# ProPrj_OSBDM_HPM5301_2024-08-18.net
KiCad netlist of a schematic drawn in EasyEDA Pro
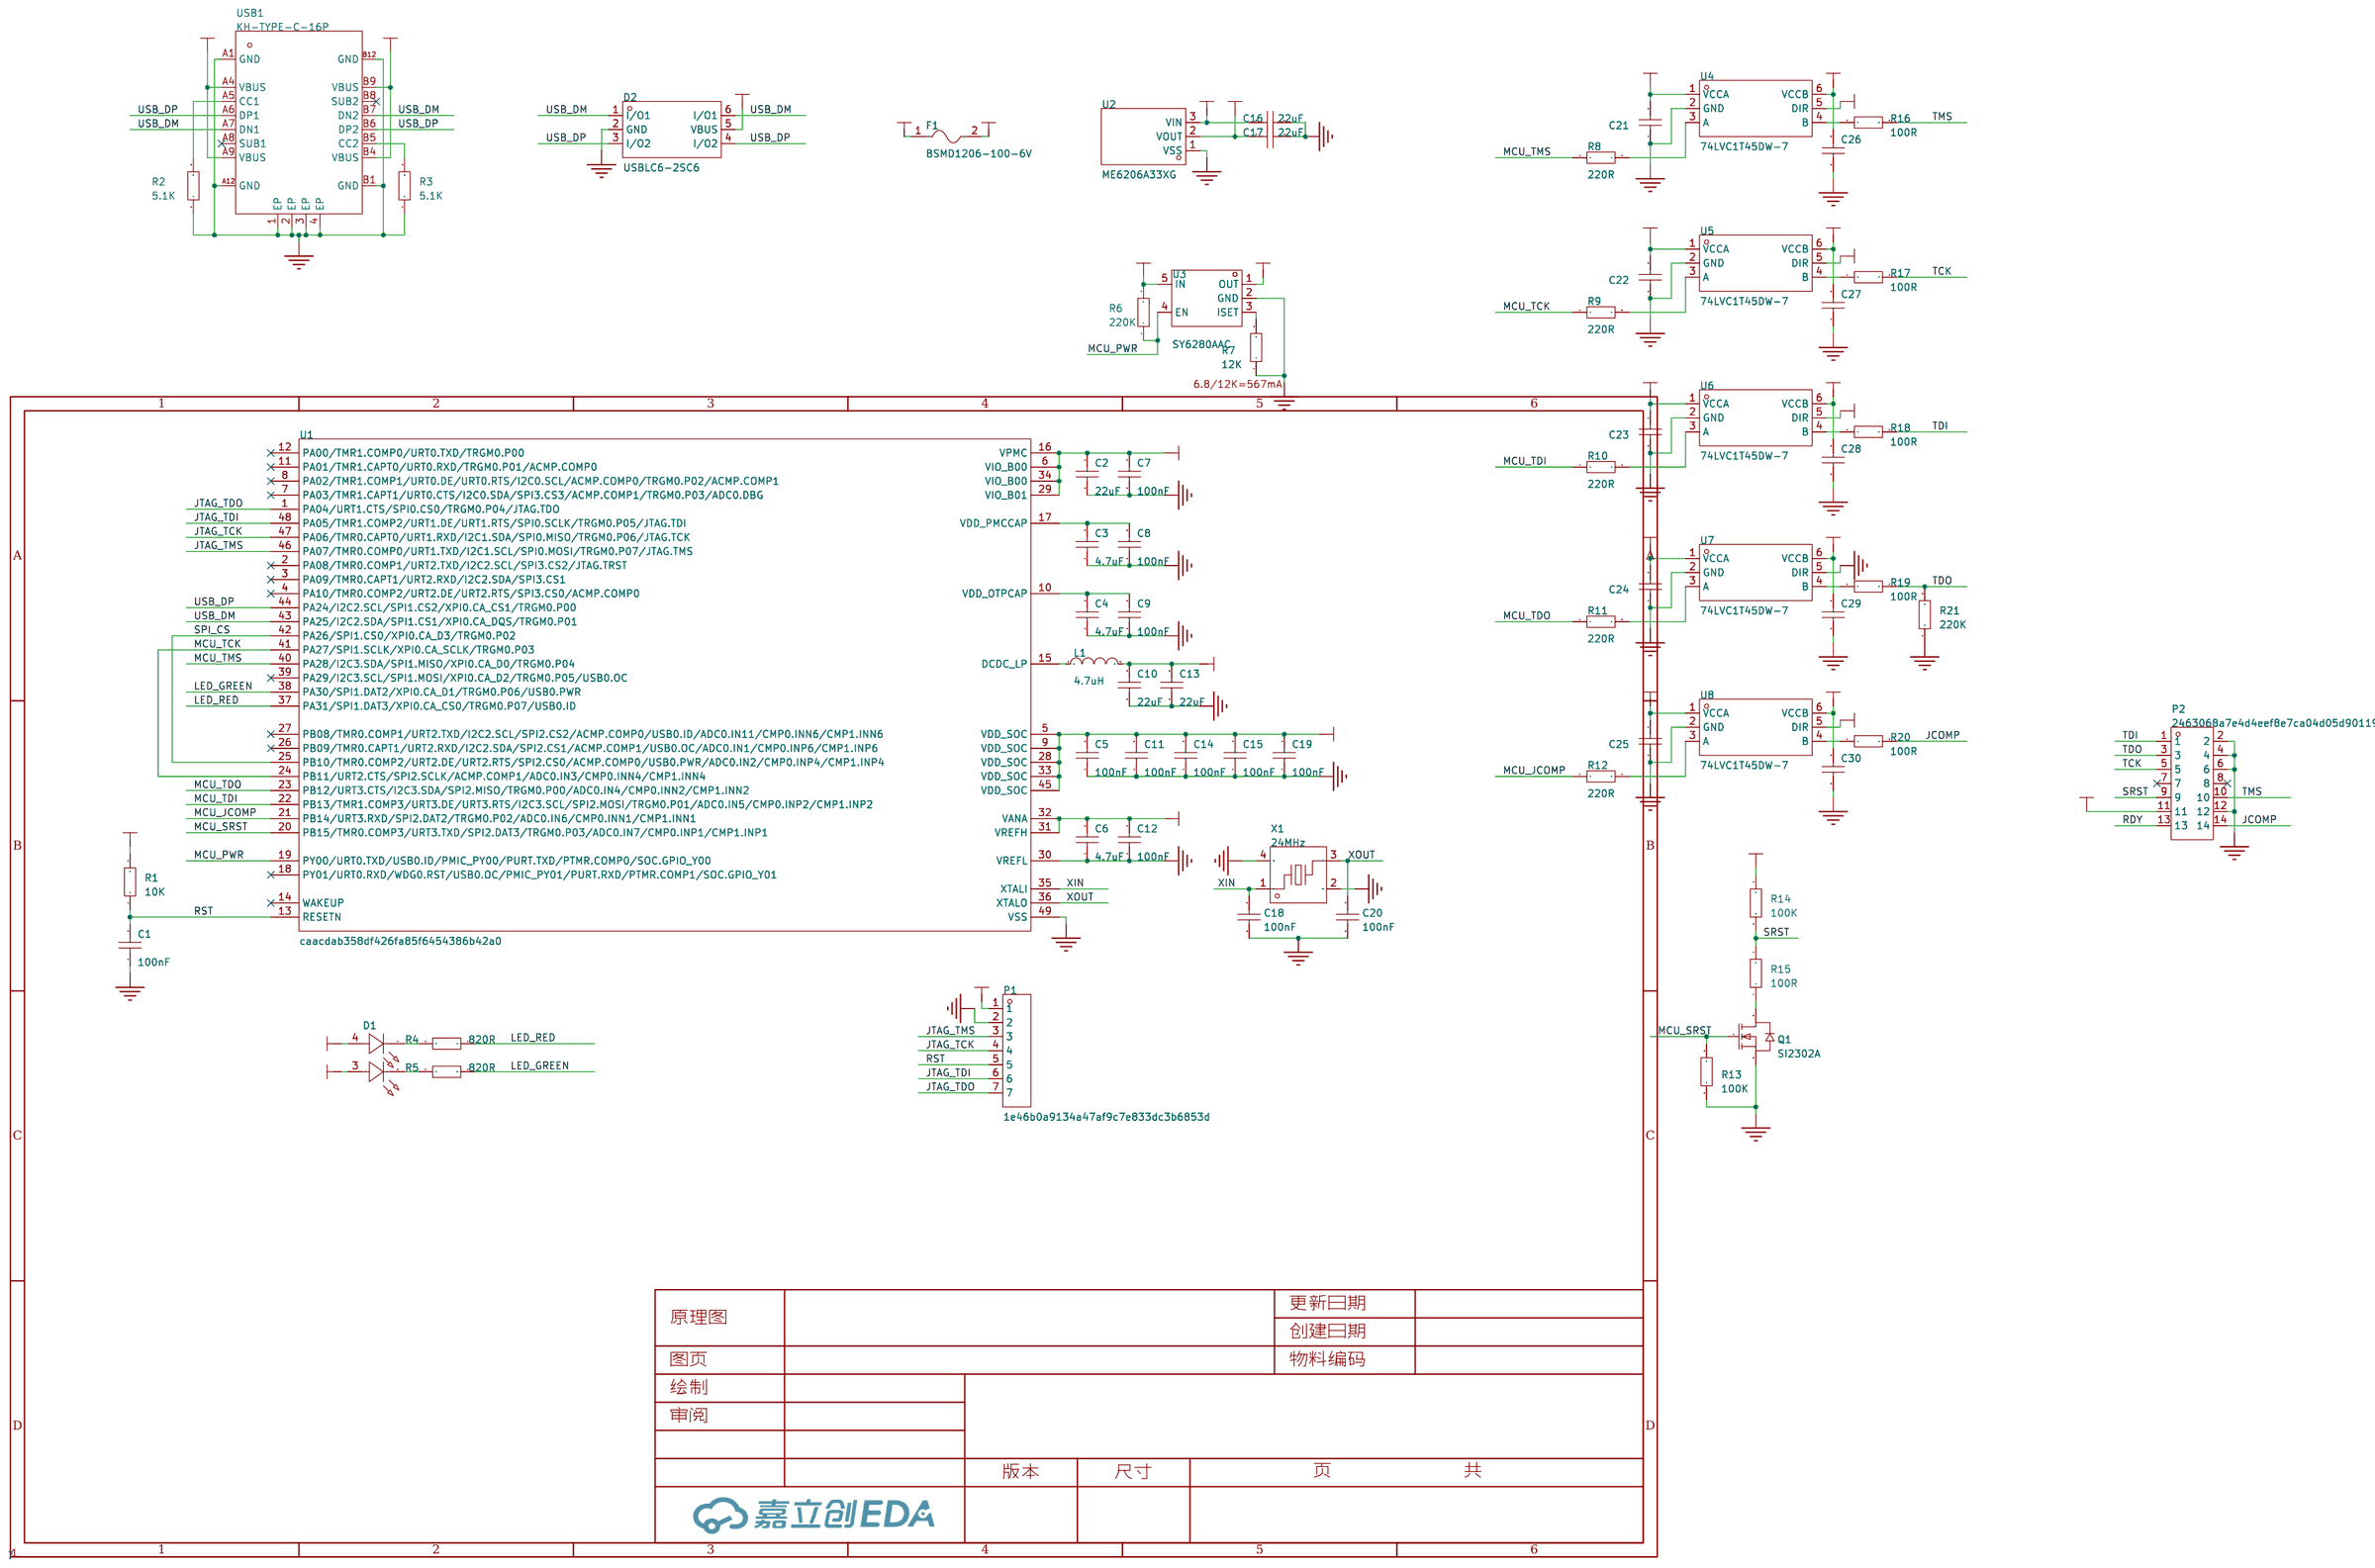
[diagram p0: schematic sheet]

(export (version "E")
  (design (tool "Eeschema 10.0.6"))
  (components
    (comp (ref "C1")
      (value "100nF")
      (footprint "easyedapro:C0603")
      (libsource (lib "easyedapro") (part "C0603"))
    )
    (comp (ref "C2")
      (value "22uF")
      (footprint "easyedapro:C0603")
      (libsource (lib "easyedapro") (part "C0603"))
    )
    (comp (ref "C3")
      (value "4.7uF")
      (footprint "easyedapro:C0603")
      (libsource (lib "easyedapro") (part "C0603"))
    )
    (comp (ref "C4")
      (value "4.7uF")
      (footprint "easyedapro:C0603")
      (libsource (lib "easyedapro") (part "C0603"))
    )
    (comp (ref "C5")
      (value "100nF")
      (footprint "easyedapro:C0603")
      (libsource (lib "easyedapro") (part "C0603"))
    )
    (comp (ref "C6")
      (value "4.7uF")
      (footprint "easyedapro:C0603")
      (libsource (lib "easyedapro") (part "C0603"))
    )
    (comp (ref "C7")
      (value "100nF")
      (footprint "easyedapro:C0603")
      (libsource (lib "easyedapro") (part "C0603"))
    )
    (comp (ref "C8")
      (value "100nF")
      (footprint "easyedapro:C0603")
      (libsource (lib "easyedapro") (part "C0603"))
    )
    (comp (ref "C9")
      (value "100nF")
      (footprint "easyedapro:C0603")
      (libsource (lib "easyedapro") (part "C0603"))
    )
    (comp (ref "C10")
      (value "22uF")
      (footprint "easyedapro:C0603")
      (libsource (lib "easyedapro") (part "C0603"))
    )
    (comp (ref "C11")
      (value "100nF")
      (footprint "easyedapro:C0603")
      (libsource (lib "easyedapro") (part "C0603"))
    )
    (comp (ref "C12")
      (value "100nF")
      (footprint "easyedapro:C0603")
      (libsource (lib "easyedapro") (part "C0603"))
    )
    (comp (ref "C13")
      (value "22uF")
      (footprint "easyedapro:C0603")
      (libsource (lib "easyedapro") (part "C0603"))
    )
    (comp (ref "C14")
      (value "100nF")
      (footprint "easyedapro:C0603")
      (libsource (lib "easyedapro") (part "C0603"))
    )
    (comp (ref "C15")
      (value "100nF")
      (footprint "easyedapro:C0603")
      (libsource (lib "easyedapro") (part "C0603"))
    )
    (comp (ref "C16")
      (value "22uF")
      (footprint "easyedapro:C0603")
      (libsource (lib "easyedapro") (part "C0603"))
    )
    (comp (ref "C17")
      (value "22uF")
      (footprint "easyedapro:C0603")
      (libsource (lib "easyedapro") (part "C0603"))
    )
    (comp (ref "C18")
      (value "100nF")
      (footprint "easyedapro:C0603")
      (libsource (lib "easyedapro") (part "C0603"))
    )
    (comp (ref "C19")
      (value "100nF")
      (footprint "easyedapro:C0603")
      (libsource (lib "easyedapro") (part "C0603"))
    )
    (comp (ref "C20")
      (value "100nF")
      (footprint "easyedapro:C0603")
      (libsource (lib "easyedapro") (part "C0603"))
    )
    (comp (ref "C21")
      (value "100nF")
      (footprint "easyedapro:C0603")
      (libsource (lib "easyedapro") (part "C0603"))
    )
    (comp (ref "C22")
      (value "100nF")
      (footprint "easyedapro:C0603")
      (libsource (lib "easyedapro") (part "C0603"))
    )
    (comp (ref "C23")
      (value "100nF")
      (footprint "easyedapro:C0603")
      (libsource (lib "easyedapro") (part "C0603"))
    )
    (comp (ref "C24")
      (value "100nF")
      (footprint "easyedapro:C0603")
      (libsource (lib "easyedapro") (part "C0603"))
    )
    (comp (ref "C25")
      (value "100nF")
      (footprint "easyedapro:C0603")
      (libsource (lib "easyedapro") (part "C0603"))
    )
    (comp (ref "C26")
      (value "100nF")
      (footprint "easyedapro:C0603")
      (libsource (lib "easyedapro") (part "C0603"))
    )
    (comp (ref "C27")
      (value "100nF")
      (footprint "easyedapro:C0603")
      (libsource (lib "easyedapro") (part "C0603"))
    )
    (comp (ref "C28")
      (value "100nF")
      (footprint "easyedapro:C0603")
      (libsource (lib "easyedapro") (part "C0603"))
    )
    (comp (ref "C29")
      (value "100nF")
      (footprint "easyedapro:C0603")
      (libsource (lib "easyedapro") (part "C0603"))
    )
    (comp (ref "C30")
      (value "100nF")
      (footprint "easyedapro:C0603")
      (libsource (lib "easyedapro") (part "C0603"))
    )
    (comp (ref "D1")
      (value "~")
      (footprint "easyedapro:LED1615")
      (libsource (lib "easyedapro") (part "LED1615"))
    )
    (comp (ref "D2")
      (value "USBLC6-2SC6")
      (footprint "easyedapro:SOT-23-6_L2.9-W1.6-P0.95-LS2.8-BL")
      (description "最大钳位电压:15V;击穿电压:6V;")
      (fields (field (name "Manufacturer") "UMW(友台半导体)"))
      (libsource (lib "easyedapro") (part "USBLC6-2SC6_C2687116"))
    )
    (comp (ref "F1")
      (value "BSMD1206-100-6V")
      (footprint "easyedapro:F1206")
      (description "最大电压:6V;最大电流:100A;保持电流:1A;跳闸电流:1.8A;")
      (fields (field (name "Manufacturer") "BHFUSE(佰宏)"))
      (libsource (lib "easyedapro") (part "BSMD1206-100-6V"))
    )
    (comp (ref "L1")
      (value "4.7uH")
      (footprint "easyedapro:IND-SMD_L2.5-W2.0")
      (description "电感值:4.7uH;精度:±20%;额定电流:840mA;饱和电流(Isat):1.25A;类型:-;")
      (fields
        (field (name "Manufacturer Part") "SWPA252012S4R7MT")
        (field (name "Manufacturer") "Sunlord(顺络)")
      )
      (libsource (lib "easyedapro") (part "SWPA252012S4R7MT"))
    )
    (comp (ref "P1")
      (value "1e46b0a9134a47af9c7e833dc3b6853d")
      (footprint "easyedapro:HDR-TH_7P-P1.27-V-M-1")
      (libsource (lib "easyedapro") (part "HDR1x7_1.27"))
    )
    (comp (ref "P2")
      (value "2463068a7e4d4eef8e7ca04d05d90119")
      (footprint "easyedapro:IDC-TH_14P-P1.27-H-F-R2-C7-W7.7")
      (description "间距：1.27mm 简牛座 弯插 2x7P 额定电流:1A，耐压:500V,工作温度范围:-40°C~+105°C")
      (libsource (lib "easyedapro") (part "IDC1.27-UD2S-7AH4.7"))
    )
    (comp (ref "Q1")
      (value "SI2302A")
      (footprint "easyedapro:SOT-23-3_L2.9-W1.3-P1.90-LS2.4-BR")
      (fields (field (name "Manufacturer") "UMW(友台半导体)"))
      (libsource (lib "easyedapro") (part "SI2302A"))
    )
    (comp (ref "R1") (value "10K") (libsource (lib "easyedapro") (part "R0402")))
    (comp (ref "R2") (value "5.1K") (libsource (lib "easyedapro") (part "R0402")))
    (comp (ref "R3") (value "5.1K") (libsource (lib "easyedapro") (part "R0402")))
    (comp (ref "R4") (value "820R") (footprint "easyedapro:R0603") (libsource (lib "easyedapro") (part "电阻")))
    (comp (ref "R5") (value "820R") (footprint "easyedapro:R0603") (libsource (lib "easyedapro") (part "电阻")))
    (comp (ref "R6")
      (value "220K")
      (footprint "easyedapro:R0603")
      (libsource (lib "easyedapro") (part "R0603"))
    )
    (comp (ref "R7")
      (value "12K")
      (footprint "easyedapro:R0603")
      (libsource (lib "easyedapro") (part "R0603"))
    )
    (comp (ref "R8")
      (value "220R")
      (footprint "easyedapro:R0603")
      (libsource (lib "easyedapro") (part "R0603"))
    )
    (comp (ref "R9")
      (value "220R")
      (footprint "easyedapro:R0603")
      (libsource (lib "easyedapro") (part "R0603"))
    )
    (comp (ref "R10")
      (value "220R")
      (footprint "easyedapro:R0603")
      (libsource (lib "easyedapro") (part "R0603"))
    )
    (comp (ref "R11")
      (value "220R")
      (footprint "easyedapro:R0603")
      (libsource (lib "easyedapro") (part "R0603"))
    )
    (comp (ref "R12")
      (value "220R")
      (footprint "easyedapro:R0603")
      (libsource (lib "easyedapro") (part "R0603"))
    )
    (comp (ref "R13")
      (value "100K")
      (footprint "easyedapro:R0603")
      (libsource (lib "easyedapro") (part "电阻"))
    )
    (comp (ref "R14")
      (value "100K")
      (footprint "easyedapro:R0603")
      (libsource (lib "easyedapro") (part "电阻"))
    )
    (comp (ref "R15")
      (value "100R")
      (footprint "easyedapro:R0603")
      (libsource (lib "easyedapro") (part "电阻"))
    )
    (comp (ref "R16")
      (value "100R")
      (footprint "easyedapro:R0603")
      (libsource (lib "easyedapro") (part "R0603"))
    )
    (comp (ref "R17")
      (value "100R")
      (footprint "easyedapro:R0603")
      (libsource (lib "easyedapro") (part "R0603"))
    )
    (comp (ref "R18")
      (value "100R")
      (footprint "easyedapro:R0603")
      (libsource (lib "easyedapro") (part "R0603"))
    )
    (comp (ref "R19")
      (value "100R")
      (footprint "easyedapro:R0603")
      (libsource (lib "easyedapro") (part "R0603"))
    )
    (comp (ref "R20")
      (value "100R")
      (footprint "easyedapro:R0603")
      (libsource (lib "easyedapro") (part "R0603"))
    )
    (comp (ref "R21")
      (value "220K")
      (footprint "easyedapro:R0603")
      (libsource (lib "easyedapro") (part "R0603"))
    )
    (comp (ref "U1")
      (value "caacdab358df426fa85f6454386b42a0")
      (footprint "easyedapro:QFN-48_L6.0-W6.0-P0.4-BL-EP4.2")
      (libsource (lib "easyedapro") (part "HPM5301IEG1"))
    )
    (comp (ref "U2")
      (value "ME6206A33XG")
      (footprint "easyedapro:SOT-23-3_L2.9-W1.6-P1.90-LS2.8-BR")
      (description "输出类型:固定;最大输入电压:6V;输出电压:3.3V;最大输出电流:300mA;电源纹波抑制比(PSRR):50dB@(1kHz);输出极性:正极;")
      (fields (field (name "Manufacturer") "MICRONE(南京微盟)"))
      (libsource (lib "easyedapro") (part "ME6206A33XG"))
    )
    (comp (ref "U3")
      (value "SY6280AAC")
      (footprint "easyedapro:SOT-23-5_L3.0-W1.7-P0.95-LS2.8-BL")
      (description "低能耗配电开关")
      (fields (field (name "Manufacturer") "silergy(矽力杰)"))
      (libsource (lib "easyedapro") (part "SY6280AAC"))
    )
    (comp (ref "U4")
      (value "74LVC1T45DW-7")
      (footprint "easyedapro:SC-70-6_L2.2-W1.3-P0.65-LS2.1-BR")
      (description "电压(VCCA):1.65V~5.5V;电压(VCCB):1.65V~5.5V;电路数:1;每个电路通道数:1;")
      (fields (field (name "Manufacturer") "DIODES(美台)"))
      (libsource (lib "easyedapro") (part "74LVC1T45DW-7"))
    )
    (comp (ref "U5")
      (value "74LVC1T45DW-7")
      (footprint "easyedapro:SC-70-6_L2.2-W1.3-P0.65-LS2.1-BR")
      (description "电压(VCCA):1.65V~5.5V;电压(VCCB):1.65V~5.5V;电路数:1;每个电路通道数:1;")
      (fields (field (name "Manufacturer") "DIODES(美台)"))
      (libsource (lib "easyedapro") (part "74LVC1T45DW-7"))
    )
    (comp (ref "U6")
      (value "74LVC1T45DW-7")
      (footprint "easyedapro:SC-70-6_L2.2-W1.3-P0.65-LS2.1-BR")
      (description "电压(VCCA):1.65V~5.5V;电压(VCCB):1.65V~5.5V;电路数:1;每个电路通道数:1;")
      (fields (field (name "Manufacturer") "DIODES(美台)"))
      (libsource (lib "easyedapro") (part "74LVC1T45DW-7"))
    )
    (comp (ref "U7")
      (value "74LVC1T45DW-7")
      (footprint "easyedapro:SC-70-6_L2.2-W1.3-P0.65-LS2.1-BR")
      (description "电压(VCCA):1.65V~5.5V;电压(VCCB):1.65V~5.5V;电路数:1;每个电路通道数:1;")
      (fields (field (name "Manufacturer") "DIODES(美台)"))
      (libsource (lib "easyedapro") (part "74LVC1T45DW-7"))
    )
    (comp (ref "U8")
      (value "74LVC1T45DW-7")
      (footprint "easyedapro:SC-70-6_L2.2-W1.3-P0.65-LS2.1-BR")
      (description "电压(VCCA):1.65V~5.5V;电压(VCCB):1.65V~5.5V;电路数:1;每个电路通道数:1;")
      (fields (field (name "Manufacturer") "DIODES(美台)"))
      (libsource (lib "easyedapro") (part "74LVC1T45DW-7"))
    )
    (comp (ref "USB1")
      (value "KH-TYPE-C-16P")
      (footprint "easyedapro:USB-C-SMD_KH-TYPE-C-16P")
      (description "连接器类型:Type-C;标准:-;公母:母座;触点数量:16;端口数量:1;安装方式:卧贴;额定电流 - 电源:3A;工作温度范围:-40~+85;")
      (fields (field (name "Manufacturer") "kinghelm(金航标)"))
      (libsource (lib "easyedapro") (part "KH-TYPE-C-16P"))
    )
    (comp (ref "X1")
      (value "24MHz")
      (footprint "easyedapro:CRYSTAL-SMD_4P-L2.0-W1.6-BL-A")
      (description "晶振类型:贴片晶振;频率:24MHz;常温频差:±10ppm;外接负载电容:8pF;频率稳定度(全温):±20ppm;")
      (fields
        (field (name "Manufacturer Part") "XL7EL89CKI-111YLC-24M")
        (field (name "Manufacturer") "YXC(扬兴晶振)")
      )
      (libsource (lib "easyedapro") (part "XL7EL89CKI-111YLC-24M"))
    )
  )
  (nets
    (net (code "1") (name "/JCOMP") (class "Default")
      (node (ref "P2") (pin "14") (pinfunction "14_14") (pintype "unspecified"))
      (node (ref "R20") (pin "2") (pinfunction "2_2") (pintype "input"))
    )
    (net (code "2") (name "/JTAG_TCK") (class "Default")
      (node (ref "P1") (pin "4") (pinfunction "4_4") (pintype "unspecified"))
      (node (ref "U1") (pin "47") (pinfunction "PA06/TMR0.CAPT0/URT1.RXD/I2C1.SDA/SPI0.MISO/TRGM0.P06/JTAG.TCK_47") (pintype "bidirectional"))
    )
    (net (code "3") (name "/JTAG_TDI") (class "Default")
      (node (ref "P1") (pin "6") (pinfunction "6_6") (pintype "unspecified"))
      (node (ref "U1") (pin "48") (pinfunction "PA05/TMR1.COMP2/URT1.DE/URT1.RTS/SPI0.SCLK/TRGM0.P05/JTAG.TDI_48") (pintype "bidirectional"))
    )
    (net (code "4") (name "/JTAG_TDO") (class "Default")
      (node (ref "P1") (pin "7") (pinfunction "7_7") (pintype "unspecified"))
      (node (ref "U1") (pin "1") (pinfunction "PA04/URT1.CTS/SPI0.CS0/TRGM0.P04/JTAG.TDO_1") (pintype "bidirectional"))
    )
    (net (code "5") (name "/JTAG_TMS") (class "Default")
      (node (ref "P1") (pin "3") (pinfunction "3_3") (pintype "unspecified"))
      (node (ref "U1") (pin "46") (pinfunction "PA07/TMR0.COMP0/URT1.TXD/I2C1.SCL/SPI0.MOSI/TRGM0.P07/JTAG.TMS_46") (pintype "bidirectional"))
    )
    (net (code "6") (name "/LED_GREEN") (class "Default")
      (node (ref "R5") (pin "1") (pinfunction "1_1") (pintype "input"))
      (node (ref "U1") (pin "38") (pinfunction "PA30/SPI1.DAT2/XPI0.CA_D1/TRGM0.P06/USB0.PWR_38") (pintype "bidirectional"))
    )
    (net (code "7") (name "/LED_RED") (class "Default")
      (node (ref "R4") (pin "1") (pinfunction "1_1") (pintype "input"))
      (node (ref "U1") (pin "37") (pinfunction "PA31/SPI1.DAT3/XPI0.CA_CS0/TRGM0.P07/USB0.ID_37") (pintype "bidirectional"))
    )
    (net (code "8") (name "/MCU_JCOMP") (class "Default")
      (node (ref "R12") (pin "1") (pinfunction "1_1") (pintype "input"))
      (node (ref "U1") (pin "21") (pinfunction "PB14/URT3.RXD/SPI2.DAT2/TRGM0.P02/ADC0.IN6/CMP0.INN1/CMP1.INN1_21") (pintype "bidirectional"))
    )
    (net (code "9") (name "/MCU_PWR") (class "Default")
      (node (ref "R6") (pin "1") (pinfunction "1_1") (pintype "input"))
      (node (ref "U1") (pin "19") (pinfunction "PY00/URT0.TXD/USB0.ID/PMIC_PY00/PURT.TXD/PTMR.COMP0/SOC.GPIO_Y00_19") (pintype "bidirectional"))
      (node (ref "U3") (pin "4") (pinfunction "EN_4") (pintype "unspecified"))
    )
    (net (code "10") (name "/MCU_SRST") (class "Default")
      (node (ref "Q1") (pin "1") (pinfunction "G_1") (pintype "unspecified"))
      (node (ref "R13") (pin "1") (pinfunction "1_1") (pintype "input"))
      (node (ref "U1") (pin "20") (pinfunction "PB15/TMR0.COMP3/URT3.TXD/SPI2.DAT3/TRGM0.P03/ADC0.IN7/CMP0.INP1/CMP1.INP1_20") (pintype "bidirectional"))
    )
    (net (code "11") (name "/MCU_TCK") (class "Default")
      (node (ref "R9") (pin "1") (pinfunction "1_1") (pintype "input"))
      (node (ref "U1") (pin "24") (pinfunction "PB11/URT2.CTS/SPI2.SCLK/ACMP.COMP1/ADC0.IN3/CMP0.INN4/CMP1.INN4_24") (pintype "bidirectional"))
      (node (ref "U1") (pin "41") (pinfunction "PA27/SPI1.SCLK/XPI0.CA_SCLK/TRGM0.P03_41") (pintype "bidirectional"))
    )
    (net (code "12") (name "/MCU_TDI") (class "Default")
      (node (ref "R10") (pin "1") (pinfunction "1_1") (pintype "input"))
      (node (ref "U1") (pin "22") (pinfunction "PB13/TMR1.COMP3/URT3.DE/URT3.RTS/I2C3.SCL/SPI2.MOSI/TRGM0.P01/ADC0.IN5/CMP0.INP2/CMP1.INP2_22") (pintype "bidirectional"))
    )
    (net (code "13") (name "/MCU_TDO") (class "Default")
      (node (ref "R11") (pin "1") (pinfunction "1_1") (pintype "input"))
      (node (ref "U1") (pin "23") (pinfunction "PB12/URT3.CTS/I2C3.SDA/SPI2.MISO/TRGM0.P00/ADC0.IN4/CMP0.INN2/CMP1.INN2_23") (pintype "bidirectional"))
    )
    (net (code "14") (name "/MCU_TMS") (class "Default")
      (node (ref "R8") (pin "1") (pinfunction "1_1") (pintype "input"))
      (node (ref "U1") (pin "40") (pinfunction "PA28/I2C3.SDA/SPI1.MISO/XPI0.CA_D0/TRGM0.P04_40") (pintype "bidirectional"))
    )
    (net (code "15") (name "/RDY") (class "Default")
      (node (ref "P2") (pin "13") (pinfunction "13_13") (pintype "unspecified"))
    )
    (net (code "16") (name "/RST") (class "Default")
      (node (ref "C1") (pin "2") (pinfunction "2_2") (pintype "input"))
      (node (ref "P1") (pin "5") (pinfunction "5_5") (pintype "unspecified"))
      (node (ref "R1") (pin "1") (pinfunction "1_1") (pintype "input"))
      (node (ref "U1") (pin "13") (pinfunction "RESETN_13") (pintype "input"))
    )
    (net (code "17") (name "/SPI_CS") (class "Default")
      (node (ref "U1") (pin "25") (pinfunction "PB10/TMR0.COMP2/URT2.DE/URT2.RTS/SPI2.CS0/ACMP.COMP0/USB0.PWR/ADC0.IN2/CMP0.INP4/CMP1.INP4_25") (pintype "bidirectional"))
      (node (ref "U1") (pin "42") (pinfunction "PA26/SPI1.CS0/XPI0.CA_D3/TRGM0.P02_42") (pintype "bidirectional"))
    )
    (net (code "18") (name "/SRST") (class "Default")
      (node (ref "P2") (pin "9") (pinfunction "9_9") (pintype "unspecified"))
      (node (ref "R14") (pin "2") (pinfunction "2_2") (pintype "input"))
      (node (ref "R15") (pin "2") (pinfunction "2_2") (pintype "input"))
    )
    (net (code "19") (name "/TCK") (class "Default")
      (node (ref "P2") (pin "5") (pinfunction "5_5") (pintype "unspecified"))
      (node (ref "R17") (pin "2") (pinfunction "2_2") (pintype "input"))
    )
    (net (code "20") (name "/TDI") (class "Default")
      (node (ref "P2") (pin "1") (pinfunction "1_1") (pintype "unspecified"))
      (node (ref "R18") (pin "2") (pinfunction "2_2") (pintype "input"))
    )
    (net (code "21") (name "/TDO") (class "Default")
      (node (ref "P2") (pin "3") (pinfunction "3_3") (pintype "unspecified"))
      (node (ref "R19") (pin "2") (pinfunction "2_2") (pintype "input"))
      (node (ref "R21") (pin "2") (pinfunction "2_2") (pintype "input"))
    )
    (net (code "22") (name "/TMS") (class "Default")
      (node (ref "P2") (pin "10") (pinfunction "10_10") (pintype "unspecified"))
      (node (ref "R16") (pin "2") (pinfunction "2_2") (pintype "input"))
    )
    (net (code "23") (name "/USB_DM") (class "Default")
      (node (ref "D2") (pin "1") (pinfunction "I/O1_1") (pintype "unspecified"))
      (node (ref "D2") (pin "6") (pinfunction "I/O1_6") (pintype "unspecified"))
      (node (ref "U1") (pin "43") (pinfunction "PA25/I2C2.SDA/SPI1.CS1/XPI0.CA_DQS/TRGM0.P01_43") (pintype "bidirectional"))
      (node (ref "USB1") (pin "A7") (pinfunction "DN1_A7") (pintype "unspecified"))
      (node (ref "USB1") (pin "B7") (pinfunction "DN2_B7") (pintype "unspecified"))
    )
    (net (code "24") (name "/USB_DP") (class "Default")
      (node (ref "D2") (pin "3") (pinfunction "I/O2_3") (pintype "unspecified"))
      (node (ref "D2") (pin "4") (pinfunction "I/O2_4") (pintype "unspecified"))
      (node (ref "U1") (pin "44") (pinfunction "PA24/I2C2.SCL/SPI1.CS2/XPI0.CA_CS1/TRGM0.P00_44") (pintype "bidirectional"))
      (node (ref "USB1") (pin "A6") (pinfunction "DP1_A6") (pintype "unspecified"))
      (node (ref "USB1") (pin "B6") (pinfunction "DP2_B6") (pintype "unspecified"))
    )
    (net (code "25") (name "/XIN") (class "Default")
      (node (ref "C18") (pin "2") (pinfunction "2_2") (pintype "input"))
      (node (ref "U1") (pin "35") (pinfunction "XTALI_35") (pintype "input"))
      (node (ref "X1") (pin "1") (pinfunction "1_1") (pintype "input"))
    )
    (net (code "26") (name "/XOUT") (class "Default")
      (node (ref "C20") (pin "2") (pinfunction "2_2") (pintype "input"))
      (node (ref "U1") (pin "36") (pinfunction "XTALO_36") (pintype "output"))
      (node (ref "X1") (pin "3") (pinfunction "3_3") (pintype "input"))
    )
    (net (code "27") (name "3.3V") (class "Default")
      (node (ref "C12") (pin "2") (pinfunction "2_2") (pintype "input"))
      (node (ref "C17") (pin "2") (pinfunction "2_2") (pintype "input"))
      (node (ref "C2") (pin "2") (pinfunction "2_2") (pintype "input"))
      (node (ref "C21") (pin "2") (pinfunction "2_2") (pintype "input"))
      (node (ref "C22") (pin "2") (pinfunction "2_2") (pintype "input"))
      (node (ref "C23") (pin "2") (pinfunction "2_2") (pintype "input"))
      (node (ref "C24") (pin "2") (pinfunction "2_2") (pintype "input"))
      (node (ref "C25") (pin "2") (pinfunction "2_2") (pintype "input"))
      (node (ref "C6") (pin "2") (pinfunction "2_2") (pintype "input"))
      (node (ref "C7") (pin "2") (pinfunction "2_2") (pintype "input"))
      (node (ref "D1") (pin "3") (pinfunction "A_3") (pintype "unspecified"))
      (node (ref "D1") (pin "4") (pinfunction "A_4") (pintype "unspecified"))
      (node (ref "P1") (pin "1") (pinfunction "1_1") (pintype "unspecified"))
      (node (ref "R1") (pin "2") (pinfunction "2_2") (pintype "input"))
      (node (ref "U1") (pin "16") (pinfunction "VPMC_16") (pintype "unspecified"))
      (node (ref "U1") (pin "29") (pinfunction "VIO_B01_29") (pintype "unspecified"))
      (node (ref "U1") (pin "31") (pinfunction "VREFH_31") (pintype "unspecified"))
      (node (ref "U1") (pin "32") (pinfunction "VANA_32") (pintype "unspecified"))
      (node (ref "U1") (pin "34") (pinfunction "VIO_B00_34") (pintype "unspecified"))
      (node (ref "U1") (pin "6") (pinfunction "VIO_B00_6") (pintype "unspecified"))
      (node (ref "U2") (pin "2") (pinfunction "VOUT_2") (pintype "input"))
      (node (ref "U4") (pin "1") (pinfunction "VCCA_1") (pintype "unspecified"))
      (node (ref "U4") (pin "5") (pinfunction "DIR_5") (pintype "unspecified"))
      (node (ref "U5") (pin "1") (pinfunction "VCCA_1") (pintype "unspecified"))
      (node (ref "U5") (pin "5") (pinfunction "DIR_5") (pintype "unspecified"))
      (node (ref "U6") (pin "1") (pinfunction "VCCA_1") (pintype "unspecified"))
      (node (ref "U6") (pin "5") (pinfunction "DIR_5") (pintype "unspecified"))
      (node (ref "U7") (pin "1") (pinfunction "VCCA_1") (pintype "unspecified"))
      (node (ref "U8") (pin "1") (pinfunction "VCCA_1") (pintype "unspecified"))
      (node (ref "U8") (pin "5") (pinfunction "DIR_5") (pintype "unspecified"))
    )
    (net (code "28") (name "5V") (class "Default")
      (node (ref "C16") (pin "2") (pinfunction "2_2") (pintype "input"))
      (node (ref "F1") (pin "2") (pinfunction "2_2") (pintype "unspecified"))
      (node (ref "R6") (pin "2") (pinfunction "2_2") (pintype "input"))
      (node (ref "U2") (pin "3") (pinfunction "VIN_3") (pintype "input"))
      (node (ref "U3") (pin "5") (pinfunction "IN_5") (pintype "unspecified"))
    )
    (net (code "29") (name "GND") (class "Default")
      (node (ref "C1") (pin "1") (pinfunction "1_1") (pintype "input"))
      (node (ref "C10") (pin "1") (pinfunction "1_1") (pintype "input"))
      (node (ref "C11") (pin "1") (pinfunction "1_1") (pintype "input"))
      (node (ref "C12") (pin "1") (pinfunction "1_1") (pintype "input"))
      (node (ref "C13") (pin "1") (pinfunction "1_1") (pintype "input"))
      (node (ref "C14") (pin "1") (pinfunction "1_1") (pintype "input"))
      (node (ref "C15") (pin "1") (pinfunction "1_1") (pintype "input"))
      (node (ref "C16") (pin "1") (pinfunction "1_1") (pintype "input"))
      (node (ref "C17") (pin "1") (pinfunction "1_1") (pintype "input"))
      (node (ref "C18") (pin "1") (pinfunction "1_1") (pintype "input"))
      (node (ref "C19") (pin "1") (pinfunction "1_1") (pintype "input"))
      (node (ref "C2") (pin "1") (pinfunction "1_1") (pintype "input"))
      (node (ref "C20") (pin "1") (pinfunction "1_1") (pintype "input"))
      (node (ref "C21") (pin "1") (pinfunction "1_1") (pintype "input"))
      (node (ref "C22") (pin "1") (pinfunction "1_1") (pintype "input"))
      (node (ref "C23") (pin "1") (pinfunction "1_1") (pintype "input"))
      (node (ref "C24") (pin "1") (pinfunction "1_1") (pintype "input"))
      (node (ref "C25") (pin "1") (pinfunction "1_1") (pintype "input"))
      (node (ref "C26") (pin "1") (pinfunction "1_1") (pintype "input"))
      (node (ref "C27") (pin "1") (pinfunction "1_1") (pintype "input"))
      (node (ref "C28") (pin "1") (pinfunction "1_1") (pintype "input"))
      (node (ref "C29") (pin "1") (pinfunction "1_1") (pintype "input"))
      (node (ref "C3") (pin "1") (pinfunction "1_1") (pintype "input"))
      (node (ref "C30") (pin "1") (pinfunction "1_1") (pintype "input"))
      (node (ref "C4") (pin "1") (pinfunction "1_1") (pintype "input"))
      (node (ref "C5") (pin "1") (pinfunction "1_1") (pintype "input"))
      (node (ref "C6") (pin "1") (pinfunction "1_1") (pintype "input"))
      (node (ref "C7") (pin "1") (pinfunction "1_1") (pintype "input"))
      (node (ref "C8") (pin "1") (pinfunction "1_1") (pintype "input"))
      (node (ref "C9") (pin "1") (pinfunction "1_1") (pintype "input"))
      (node (ref "D2") (pin "2") (pinfunction "GND_2") (pintype "unspecified"))
      (node (ref "P1") (pin "2") (pinfunction "2_2") (pintype "unspecified"))
      (node (ref "P2") (pin "12") (pinfunction "12_12") (pintype "unspecified"))
      (node (ref "P2") (pin "2") (pinfunction "2_2") (pintype "unspecified"))
      (node (ref "P2") (pin "4") (pinfunction "4_4") (pintype "unspecified"))
      (node (ref "P2") (pin "6") (pinfunction "6_6") (pintype "unspecified"))
      (node (ref "Q1") (pin "2") (pinfunction "S_2") (pintype "unspecified"))
      (node (ref "R13") (pin "2") (pinfunction "2_2") (pintype "input"))
      (node (ref "R2") (pin "1") (pinfunction "1_1") (pintype "input"))
      (node (ref "R21") (pin "1") (pinfunction "1_1") (pintype "input"))
      (node (ref "R3") (pin "1") (pinfunction "1_1") (pintype "input"))
      (node (ref "R7") (pin "1") (pinfunction "1_1") (pintype "input"))
      (node (ref "U1") (pin "30") (pinfunction "VREFL_30") (pintype "unspecified"))
      (node (ref "U1") (pin "49") (pinfunction "VSS_49") (pintype "unspecified"))
      (node (ref "U2") (pin "1") (pinfunction "VSS_1") (pintype "input"))
      (node (ref "U3") (pin "2") (pinfunction "GND_2") (pintype "unspecified"))
      (node (ref "U4") (pin "2") (pinfunction "GND_2") (pintype "unspecified"))
      (node (ref "U5") (pin "2") (pinfunction "GND_2") (pintype "unspecified"))
      (node (ref "U6") (pin "2") (pinfunction "GND_2") (pintype "unspecified"))
      (node (ref "U7") (pin "2") (pinfunction "GND_2") (pintype "unspecified"))
      (node (ref "U7") (pin "5") (pinfunction "DIR_5") (pintype "unspecified"))
      (node (ref "U8") (pin "2") (pinfunction "GND_2") (pintype "unspecified"))
      (node (ref "USB1") (pin "1") (pinfunction "EP_1") (pintype "unspecified"))
      (node (ref "USB1") (pin "2") (pinfunction "EP_2") (pintype "unspecified"))
      (node (ref "USB1") (pin "3") (pinfunction "EP_3") (pintype "unspecified"))
      (node (ref "USB1") (pin "4") (pinfunction "EP_4") (pintype "unspecified"))
      (node (ref "USB1") (pin "A1") (pinfunction "GND_A1") (pintype "unspecified"))
      (node (ref "USB1") (pin "A12") (pinfunction "GND_A12") (pintype "unspecified"))
      (node (ref "USB1") (pin "B1") (pinfunction "GND_B1") (pintype "unspecified"))
      (node (ref "USB1") (pin "B12") (pinfunction "GND_B12") (pintype "unspecified"))
      (node (ref "X1") (pin "2") (pinfunction "GND_2") (pintype "input"))
      (node (ref "X1") (pin "4") (pinfunction "GND_4") (pintype "input"))
    )
    (net (code "30") (name "Net-(D1-K-Pad1)") (class "Default")
      (node (ref "D1") (pin "1") (pinfunction "K_1") (pintype "unspecified"))
      (node (ref "R4") (pin "2") (pinfunction "2_2") (pintype "input"))
    )
    (net (code "31") (name "Net-(D1-K-Pad2)") (class "Default")
      (node (ref "D1") (pin "2") (pinfunction "K_2") (pintype "unspecified"))
      (node (ref "R5") (pin "2") (pinfunction "2_2") (pintype "input"))
    )
    (net (code "32") (name "Net-(Q1-D)") (class "Default")
      (node (ref "Q1") (pin "3") (pinfunction "D_3") (pintype "unspecified"))
      (node (ref "R15") (pin "1") (pinfunction "1_1") (pintype "input"))
    )
    (net (code "33") (name "Net-(U1-DCDC_LP)") (class "Default")
      (node (ref "L1") (pin "1") (pinfunction "1_1") (pintype "unspecified"))
      (node (ref "U1") (pin "15") (pinfunction "DCDC_LP_15") (pintype "unspecified"))
    )
    (net (code "34") (name "Net-(U1-VDD_OTPCAP)") (class "Default")
      (node (ref "C4") (pin "2") (pinfunction "2_2") (pintype "input"))
      (node (ref "C9") (pin "2") (pinfunction "2_2") (pintype "input"))
      (node (ref "U1") (pin "10") (pinfunction "VDD_OTPCAP_10") (pintype "unspecified"))
    )
    (net (code "35") (name "Net-(U1-VDD_PMCCAP)") (class "Default")
      (node (ref "C3") (pin "2") (pinfunction "2_2") (pintype "input"))
      (node (ref "C8") (pin "2") (pinfunction "2_2") (pintype "input"))
      (node (ref "U1") (pin "17") (pinfunction "VDD_PMCCAP_17") (pintype "unspecified"))
    )
    (net (code "36") (name "Net-(U3-ISET)") (class "Default")
      (node (ref "R7") (pin "2") (pinfunction "2_2") (pintype "input"))
      (node (ref "U3") (pin "3") (pinfunction "ISET_3") (pintype "unspecified"))
    )
    (net (code "37") (name "Net-(U4-A)") (class "Default")
      (node (ref "R8") (pin "2") (pinfunction "2_2") (pintype "input"))
      (node (ref "U4") (pin "3") (pinfunction "A_3") (pintype "unspecified"))
    )
    (net (code "38") (name "Net-(U4-B)") (class "Default")
      (node (ref "R16") (pin "1") (pinfunction "1_1") (pintype "input"))
      (node (ref "U4") (pin "4") (pinfunction "B_4") (pintype "unspecified"))
    )
    (net (code "39") (name "Net-(U5-A)") (class "Default")
      (node (ref "R9") (pin "2") (pinfunction "2_2") (pintype "input"))
      (node (ref "U5") (pin "3") (pinfunction "A_3") (pintype "unspecified"))
    )
    (net (code "40") (name "Net-(U5-B)") (class "Default")
      (node (ref "R17") (pin "1") (pinfunction "1_1") (pintype "input"))
      (node (ref "U5") (pin "4") (pinfunction "B_4") (pintype "unspecified"))
    )
    (net (code "41") (name "Net-(U6-A)") (class "Default")
      (node (ref "R10") (pin "2") (pinfunction "2_2") (pintype "input"))
      (node (ref "U6") (pin "3") (pinfunction "A_3") (pintype "unspecified"))
    )
    (net (code "42") (name "Net-(U6-B)") (class "Default")
      (node (ref "R18") (pin "1") (pinfunction "1_1") (pintype "input"))
      (node (ref "U6") (pin "4") (pinfunction "B_4") (pintype "unspecified"))
    )
    (net (code "43") (name "Net-(U7-A)") (class "Default")
      (node (ref "R11") (pin "2") (pinfunction "2_2") (pintype "input"))
      (node (ref "U7") (pin "3") (pinfunction "A_3") (pintype "unspecified"))
    )
    (net (code "44") (name "Net-(U7-B)") (class "Default")
      (node (ref "R19") (pin "1") (pinfunction "1_1") (pintype "input"))
      (node (ref "U7") (pin "4") (pinfunction "B_4") (pintype "unspecified"))
    )
    (net (code "45") (name "Net-(U8-A)") (class "Default")
      (node (ref "R12") (pin "2") (pinfunction "2_2") (pintype "input"))
      (node (ref "U8") (pin "3") (pinfunction "A_3") (pintype "unspecified"))
    )
    (net (code "46") (name "Net-(U8-B)") (class "Default")
      (node (ref "R20") (pin "1") (pinfunction "1_1") (pintype "input"))
      (node (ref "U8") (pin "4") (pinfunction "B_4") (pintype "unspecified"))
    )
    (net (code "47") (name "Net-(USB1-CC1)") (class "Default")
      (node (ref "R2") (pin "2") (pinfunction "2_2") (pintype "input"))
      (node (ref "USB1") (pin "A5") (pinfunction "CC1_A5") (pintype "unspecified"))
    )
    (net (code "48") (name "Net-(USB1-CC2)") (class "Default")
      (node (ref "R3") (pin "2") (pinfunction "2_2") (pintype "input"))
      (node (ref "USB1") (pin "B5") (pinfunction "CC2_B5") (pintype "unspecified"))
    )
    (net (code "49") (name "VBUS") (class "Default")
      (node (ref "D2") (pin "5") (pinfunction "VBUS_5") (pintype "unspecified"))
      (node (ref "F1") (pin "1") (pinfunction "1_1") (pintype "unspecified"))
      (node (ref "USB1") (pin "A4") (pinfunction "VBUS_A4") (pintype "unspecified"))
      (node (ref "USB1") (pin "A9") (pinfunction "VBUS_A9") (pintype "unspecified"))
      (node (ref "USB1") (pin "B4") (pinfunction "VBUS_B4") (pintype "unspecified"))
      (node (ref "USB1") (pin "B9") (pinfunction "VBUS_B9") (pintype "unspecified"))
    )
    (net (code "50") (name "VDD_SOC") (class "Default")
      (node (ref "C10") (pin "2") (pinfunction "2_2") (pintype "input"))
      (node (ref "C11") (pin "2") (pinfunction "2_2") (pintype "input"))
      (node (ref "C13") (pin "2") (pinfunction "2_2") (pintype "input"))
      (node (ref "C14") (pin "2") (pinfunction "2_2") (pintype "input"))
      (node (ref "C15") (pin "2") (pinfunction "2_2") (pintype "input"))
      (node (ref "C19") (pin "2") (pinfunction "2_2") (pintype "input"))
      (node (ref "C5") (pin "2") (pinfunction "2_2") (pintype "input"))
      (node (ref "L1") (pin "2") (pinfunction "2_2") (pintype "unspecified"))
      (node (ref "U1") (pin "28") (pinfunction "VDD_SOC_28") (pintype "unspecified"))
      (node (ref "U1") (pin "33") (pinfunction "VDD_SOC_33") (pintype "unspecified"))
      (node (ref "U1") (pin "45") (pinfunction "VDD_SOC_45") (pintype "unspecified"))
      (node (ref "U1") (pin "5") (pinfunction "VDD_SOC_5") (pintype "unspecified"))
      (node (ref "U1") (pin "9") (pinfunction "VDD_SOC_9") (pintype "unspecified"))
    )
    (net (code "51") (name "VREF") (class "Default")
      (node (ref "C26") (pin "2") (pinfunction "2_2") (pintype "input"))
      (node (ref "C27") (pin "2") (pinfunction "2_2") (pintype "input"))
      (node (ref "C28") (pin "2") (pinfunction "2_2") (pintype "input"))
      (node (ref "C29") (pin "2") (pinfunction "2_2") (pintype "input"))
      (node (ref "C30") (pin "2") (pinfunction "2_2") (pintype "input"))
      (node (ref "P2") (pin "11") (pinfunction "11_11") (pintype "unspecified"))
      (node (ref "R14") (pin "1") (pinfunction "1_1") (pintype "input"))
      (node (ref "U3") (pin "1") (pinfunction "OUT_1") (pintype "unspecified"))
      (node (ref "U4") (pin "6") (pinfunction "VCCB_6") (pintype "unspecified"))
      (node (ref "U5") (pin "6") (pinfunction "VCCB_6") (pintype "unspecified"))
      (node (ref "U6") (pin "6") (pinfunction "VCCB_6") (pintype "unspecified"))
      (node (ref "U7") (pin "6") (pinfunction "VCCB_6") (pintype "unspecified"))
      (node (ref "U8") (pin "6") (pinfunction "VCCB_6") (pintype "unspecified"))
    )
    (net (code "52") (name "unconnected-(P2-Pad7)") (class "Default")
      (node (ref "P2") (pin "7") (pinfunction "7_7") (pintype "unspecified+no_connect"))
    )
    (net (code "53") (name "unconnected-(P2-Pad8)") (class "Default")
      (node (ref "P2") (pin "8") (pinfunction "8_8") (pintype "unspecified+no_connect"))
    )
    (net (code "54") (name "unconnected-(U1-PA00{slash}TMR1.COMP0{slash}URT0.TXD{slash}TRGM0.P00-Pad12)") (class "Default")
      (node (ref "U1") (pin "12") (pinfunction "PA00/TMR1.COMP0/URT0.TXD/TRGM0.P00_12") (pintype "bidirectional+no_connect"))
    )
    (net (code "55") (name "unconnected-(U1-PA01{slash}TMR1.CAPT0{slash}URT0.RXD{slash}TRGM0.P01{slash}ACMP.COMP0-Pad11)") (class "Default")
      (node (ref "U1") (pin "11") (pinfunction "PA01/TMR1.CAPT0/URT0.RXD/TRGM0.P01/ACMP.COMP0_11") (pintype "bidirectional+no_connect"))
    )
    (net (code "56") (name "unconnected-(U1-PA02{slash}TMR1.COMP1{slash}URT0.DE{slash}URT0.RTS{slash}I2C0.SCL{slash}ACMP.COMP0{slash}TRGM0.P02{slash}ACMP.COMP1-Pad8)") (class "Default")
      (node (ref "U1") (pin "8") (pinfunction "PA02/TMR1.COMP1/URT0.DE/URT0.RTS/I2C0.SCL/ACMP.COMP0/TRGM0.P02/ACMP.COMP1_8") (pintype "bidirectional+no_connect"))
    )
    (net (code "57") (name "unconnected-(U1-PA03{slash}TMR1.CAPT1{slash}URT0.CTS{slash}I2C0.SDA{slash}SPI3.CS3{slash}ACMP.COMP1{slash}TRGM0.P03{slash}ADC0.DBG-Pad7)") (class "Default")
      (node (ref "U1") (pin "7") (pinfunction "PA03/TMR1.CAPT1/URT0.CTS/I2C0.SDA/SPI3.CS3/ACMP.COMP1/TRGM0.P03/ADC0.DBG_7") (pintype "bidirectional+no_connect"))
    )
    (net (code "58") (name "unconnected-(U1-PA08{slash}TMR0.COMP1{slash}URT2.TXD{slash}I2C2.SCL{slash}SPI3.CS2{slash}JTAG.TRST-Pad2)") (class "Default")
      (node (ref "U1") (pin "2") (pinfunction "PA08/TMR0.COMP1/URT2.TXD/I2C2.SCL/SPI3.CS2/JTAG.TRST_2") (pintype "bidirectional+no_connect"))
    )
    (net (code "59") (name "unconnected-(U1-PA09{slash}TMR0.CAPT1{slash}URT2.RXD{slash}I2C2.SDA{slash}SPI3.CS1-Pad3)") (class "Default")
      (node (ref "U1") (pin "3") (pinfunction "PA09/TMR0.CAPT1/URT2.RXD/I2C2.SDA/SPI3.CS1_3") (pintype "bidirectional+no_connect"))
    )
    (net (code "60") (name "unconnected-(U1-PA10{slash}TMR0.COMP2{slash}URT2.DE{slash}URT2.RTS{slash}SPI3.CS0{slash}ACMP.COMP0-Pad4)") (class "Default")
      (node (ref "U1") (pin "4") (pinfunction "PA10/TMR0.COMP2/URT2.DE/URT2.RTS/SPI3.CS0/ACMP.COMP0_4") (pintype "bidirectional+no_connect"))
    )
    (net (code "61") (name "unconnected-(U1-PA29{slash}I2C3.SCL{slash}SPI1.MOSI{slash}XPI0.CA_D2{slash}TRGM0.P05{slash}USB0.OC-Pad39)") (class "Default")
      (node (ref "U1") (pin "39") (pinfunction "PA29/I2C3.SCL/SPI1.MOSI/XPI0.CA_D2/TRGM0.P05/USB0.OC_39") (pintype "bidirectional+no_connect"))
    )
    (net (code "62") (name "unconnected-(U1-PB08{slash}TMR0.COMP1{slash}URT2.TXD{slash}I2C2.SCL{slash}SPI2.CS2{slash}ACMP.COMP0{slash}USB0.ID{slash}ADC0.IN11{slash}CMP0.INN6{slash}CMP1.INN6-Pad27)") (class "Default")
      (node (ref "U1") (pin "27") (pinfunction "PB08/TMR0.COMP1/URT2.TXD/I2C2.SCL/SPI2.CS2/ACMP.COMP0/USB0.ID/ADC0.IN11/CMP0.INN6/CMP1.INN6_27") (pintype "bidirectional+no_connect"))
    )
    (net (code "63") (name "unconnected-(U1-PB09{slash}TMR0.CAPT1{slash}URT2.RXD{slash}I2C2.SDA{slash}SPI2.CS1{slash}ACMP.COMP1{slash}USB0.OC{slash}ADC0.IN1{slash}CMP0.INP6{slash}CMP1.INP6-Pad26)") (class "Default")
      (node (ref "U1") (pin "26") (pinfunction "PB09/TMR0.CAPT1/URT2.RXD/I2C2.SDA/SPI2.CS1/ACMP.COMP1/USB0.OC/ADC0.IN1/CMP0.INP6/CMP1.INP6_26") (pintype "bidirectional+no_connect"))
    )
    (net (code "64") (name "unconnected-(U1-PY01{slash}URT0.RXD{slash}WDG0.RST{slash}USB0.OC{slash}PMIC_PY01{slash}PURT.RXD{slash}PTMR.COMP1{slash}SOC.GPIO_Y01-Pad18)") (class "Default")
      (node (ref "U1") (pin "18") (pinfunction "PY01/URT0.RXD/WDG0.RST/USB0.OC/PMIC_PY01/PURT.RXD/PTMR.COMP1/SOC.GPIO_Y01_18") (pintype "bidirectional+no_connect"))
    )
    (net (code "65") (name "unconnected-(U1-WAKEUP-Pad14)") (class "Default")
      (node (ref "U1") (pin "14") (pinfunction "WAKEUP_14") (pintype "input+no_connect"))
    )
    (net (code "66") (name "unconnected-(USB1-SUB1-PadA8)") (class "Default")
      (node (ref "USB1") (pin "A8") (pinfunction "SUB1_A8") (pintype "unspecified+no_connect"))
    )
    (net (code "67") (name "unconnected-(USB1-SUB2-PadB8)") (class "Default")
      (node (ref "USB1") (pin "B8") (pinfunction "SUB2_B8") (pintype "unspecified+no_connect"))
    )
  )
)
